# STM.net
KiCad netlist of a schematic drawn in EAGLE
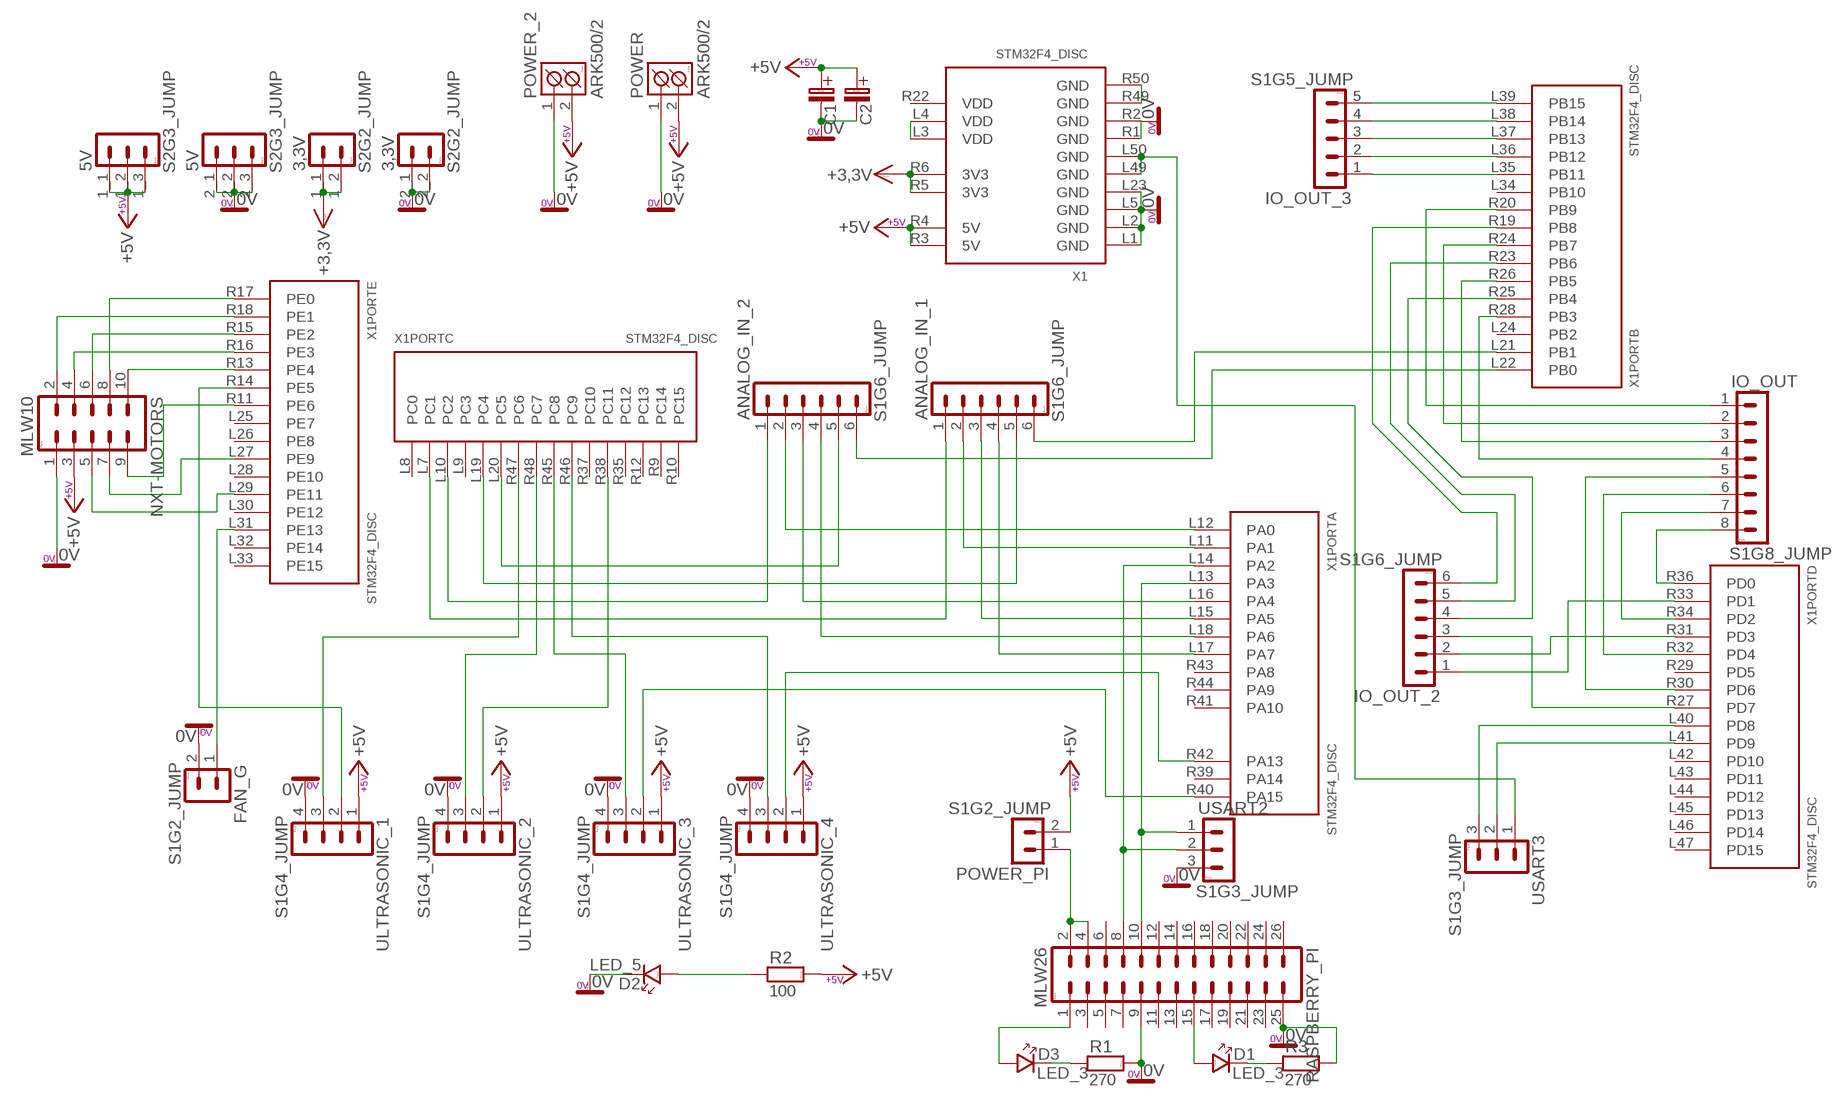
[diagram p0: schematic, sheet 1]

(export (version "E")
  (design (tool "Eeschema 10.0.6"))
  (components
    (comp (ref "3,3V")
      (value "S2G2_JUMP")
      (footprint "eagle-import:S2G2_JUM")
      (libsource (lib "eagle-import") (part "S2G2_JUMP"))
    )
    (comp (ref "5V")
      (value "S2G3_JUMP")
      (footprint "eagle-import:S2G3_JUM")
      (libsource (lib "eagle-import") (part "S2G3_JUMP"))
    )
    (comp (ref "ANALOG_IN_1")
      (value "S1G6_JUMP")
      (footprint "eagle-import:S1G6_JUM")
      (libsource (lib "eagle-import") (part "S1G6_JUMP"))
    )
    (comp (ref "ANALOG_IN_2")
      (value "S1G6_JUMP")
      (footprint "eagle-import:S1G6_JUM")
      (libsource (lib "eagle-import") (part "S1G6_JUMP"))
    )
    (comp (ref "C1")
      (value "#_RADIAL_POUZDRA5")
      (footprint "eagle-import:C_EL_5")
      (libsource (lib "eagle-import") (part "#_RADIAL_POUZDRA5"))
    )
    (comp (ref "C2")
      (value "#_RADIAL_POUZDRA5")
      (footprint "eagle-import:C_EL_5")
      (libsource (lib "eagle-import") (part "#_RADIAL_POUZDRA5"))
    )
    (comp (ref "D1")
      (value "LED_3")
      (footprint "eagle-import:LED_3")
      (libsource (lib "eagle-import") (part "LED_3"))
    )
    (comp (ref "D2")
      (value "LED_5")
      (footprint "eagle-import:LED_5")
      (libsource (lib "eagle-import") (part "LED_5"))
    )
    (comp (ref "D3")
      (value "LED_3")
      (footprint "eagle-import:LED_3")
      (libsource (lib "eagle-import") (part "LED_3"))
    )
    (comp (ref "FAN_G")
      (value "S1G2_JUMP")
      (footprint "eagle-import:S1G2_JUM")
      (libsource (lib "eagle-import") (part "S1G2_JUMP"))
    )
    (comp (ref "IO_OUT")
      (value "S1G8_JUMP")
      (footprint "eagle-import:S1G8_JUM")
      (libsource (lib "eagle-import") (part "S1G8_JUMP"))
    )
    (comp (ref "IO_OUT_2")
      (value "S1G6_JUMP")
      (footprint "eagle-import:S1G6_JUM")
      (libsource (lib "eagle-import") (part "S1G6_JUMP"))
    )
    (comp (ref "IO_OUT_3")
      (value "S1G5_JUMP")
      (footprint "eagle-import:S1G5_JUM")
      (libsource (lib "eagle-import") (part "S1G5_JUMP"))
    )
    (comp (ref "NXT-MOTORS")
      (value "MLW10")
      (footprint "eagle-import:MLW10G")
      (libsource (lib "eagle-import") (part "MLW10"))
    )
    (comp (ref "POWER")
      (value "ARK500/2")
      (footprint "eagle-import:ARK500_2")
      (libsource (lib "eagle-import") (part "ARK500/2"))
    )
    (comp (ref "POWER_2")
      (value "ARK500/2")
      (footprint "eagle-import:ARK500_2")
      (libsource (lib "eagle-import") (part "ARK500/2"))
    )
    (comp (ref "POWER_PI")
      (value "S1G2_JUMP")
      (footprint "eagle-import:S1G2_JUM")
      (libsource (lib "eagle-import") (part "S1G2_JUMP"))
    )
    (comp (ref "R1")
      (value "270")
      (footprint "eagle-import:R_7,5")
      (libsource (lib "eagle-import") (part "4K7"))
    )
    (comp (ref "R2")
      (value "100")
      (footprint "eagle-import:R_7,5")
      (libsource (lib "eagle-import") (part "100R"))
    )
    (comp (ref "R3")
      (value "270")
      (footprint "eagle-import:R_7,5")
      (libsource (lib "eagle-import") (part "4K7"))
    )
    (comp (ref "RASPBERRY_PI")
      (value "MLW26")
      (footprint "eagle-import:MLW26G")
      (libsource (lib "eagle-import") (part "MLW26"))
    )
    (comp (ref "ULTRASONIC_1")
      (value "S1G4_JUMP")
      (footprint "eagle-import:S1G4_JUM")
      (libsource (lib "eagle-import") (part "S1G4_JUMP"))
    )
    (comp (ref "ULTRASONIC_2")
      (value "S1G4_JUMP")
      (footprint "eagle-import:S1G4_JUM")
      (libsource (lib "eagle-import") (part "S1G4_JUMP"))
    )
    (comp (ref "ULTRASONIC_3")
      (value "S1G4_JUMP")
      (footprint "eagle-import:S1G4_JUM")
      (libsource (lib "eagle-import") (part "S1G4_JUMP"))
    )
    (comp (ref "ULTRASONIC_4")
      (value "S1G4_JUMP")
      (footprint "eagle-import:S1G4_JUM")
      (libsource (lib "eagle-import") (part "S1G4_JUMP"))
    )
    (comp (ref "USART2")
      (value "S1G3_JUMP")
      (footprint "eagle-import:S1G3_JUM")
      (libsource (lib "eagle-import") (part "S1G3_JUMP"))
    )
    (comp (ref "USART3")
      (value "S1G3_JUMP")
      (footprint "eagle-import:S1G3_JUM")
      (libsource (lib "eagle-import") (part "S1G3_JUMP"))
    )
    (comp (ref "X1")
      (value "STM32F4_DISC")
      (footprint "eagle-import:STM32F4_DISC")
      (libsource (lib "eagle-import") (part "STM32F4_DISC"))
    )
  )
  (nets
    (net (code "1") (name "+3,3V") (class "Default")
      (node (ref "3,3V") (pin "1_1") (pinfunction "1_1_1") (pintype "passive"))
      (node (ref "3,3V") (pin "1_2") (pinfunction "2_1_2") (pintype "passive"))
      (node (ref "X1") (pin "R5") (pinfunction "3V3_R5") (pintype "power_in"))
      (node (ref "X1") (pin "R6") (pinfunction "3V3_R6") (pintype "power_in"))
    )
    (net (code "2") (name "+5V") (class "Default")
      (node (ref "5V") (pin "1_1") (pinfunction "1_1_1") (pintype "passive"))
      (node (ref "5V") (pin "1_2") (pinfunction "2_1_2") (pintype "passive"))
      (node (ref "5V") (pin "1_3") (pinfunction "3_1_3") (pintype "passive"))
      (node (ref "C1") (pin "C+") (pinfunction "C_EL+_C+") (pintype "passive"))
      (node (ref "C2") (pin "C+") (pinfunction "C_EL+_C+") (pintype "passive"))
      (node (ref "NXT-MOTORS") (pin "3") (pinfunction "3_3") (pintype "passive"))
      (node (ref "POWER") (pin "2") (pinfunction "K2_2") (pintype "passive"))
      (node (ref "POWER_2") (pin "2") (pinfunction "K2_2") (pintype "passive"))
      (node (ref "POWER_PI") (pin "2") (pinfunction "2_2") (pintype "passive"))
      (node (ref "R2") (pin "2") (pinfunction "2_2") (pintype "passive"))
      (node (ref "ULTRASONIC_1") (pin "1") (pinfunction "1_1") (pintype "passive"))
      (node (ref "ULTRASONIC_2") (pin "1") (pinfunction "1_1") (pintype "passive"))
      (node (ref "ULTRASONIC_3") (pin "1") (pinfunction "1_1") (pintype "passive"))
      (node (ref "ULTRASONIC_4") (pin "1") (pinfunction "1_1") (pintype "passive"))
      (node (ref "X1") (pin "R3") (pinfunction "5V_R3") (pintype "power_in"))
      (node (ref "X1") (pin "R4") (pinfunction "5V_R4") (pintype "power_in"))
    )
    (net (code "3") (name "/VDD") (class "Default")
      (node (ref "X1") (pin "R22") (pinfunction "VDD_R22") (pintype "power_in"))
    )
    (net (code "4") (name "0V") (class "Default")
      (node (ref "3,3V") (pin "2_1") (pinfunction "1_2_1") (pintype "passive"))
      (node (ref "3,3V") (pin "2_2") (pinfunction "2_2_2") (pintype "passive"))
      (node (ref "5V") (pin "2_1") (pinfunction "1_2_1") (pintype "passive"))
      (node (ref "5V") (pin "2_2") (pinfunction "2_2_2") (pintype "passive"))
      (node (ref "5V") (pin "2_3") (pinfunction "3_2_3") (pintype "passive"))
      (node (ref "C1") (pin "C-") (pinfunction "C_EL-_C-") (pintype "passive"))
      (node (ref "C2") (pin "C-") (pinfunction "C_EL-_C-") (pintype "passive"))
      (node (ref "D2") (pin "K") (pinfunction "K_K") (pintype "passive"))
      (node (ref "FAN_G") (pin "2") (pinfunction "2_2") (pintype "passive"))
      (node (ref "NXT-MOTORS") (pin "1") (pinfunction "1_1") (pintype "passive"))
      (node (ref "POWER") (pin "1") (pinfunction "K1_1") (pintype "passive"))
      (node (ref "POWER_2") (pin "1") (pinfunction "K1_1") (pintype "passive"))
      (node (ref "R1") (pin "2") (pinfunction "2_2") (pintype "passive"))
      (node (ref "R3") (pin "2") (pinfunction "2_2") (pintype "passive"))
      (node (ref "RASPBERRY_PI") (pin "25") (pinfunction "25_25") (pintype "passive"))
      (node (ref "RASPBERRY_PI") (pin "9") (pinfunction "9_9") (pintype "passive"))
      (node (ref "ULTRASONIC_1") (pin "4") (pinfunction "4_4") (pintype "passive"))
      (node (ref "ULTRASONIC_2") (pin "4") (pinfunction "4_4") (pintype "passive"))
      (node (ref "ULTRASONIC_3") (pin "4") (pinfunction "4_4") (pintype "passive"))
      (node (ref "ULTRASONIC_4") (pin "4") (pinfunction "4_4") (pintype "passive"))
      (node (ref "USART2") (pin "3") (pinfunction "3_3") (pintype "passive"))
      (node (ref "X1") (pin "L1") (pinfunction "GND_L1") (pintype "power_in"))
      (node (ref "X1") (pin "L2") (pinfunction "GND_L2") (pintype "power_in"))
      (node (ref "X1") (pin "L23") (pinfunction "GND_L23") (pintype "power_in"))
      (node (ref "X1") (pin "L5") (pinfunction "GND_L5") (pintype "power_in"))
      (node (ref "X1") (pin "R1") (pinfunction "GND_R1") (pintype "power_in"))
      (node (ref "X1") (pin "R2") (pinfunction "GND_R2") (pintype "power_in"))
    )
    (net (code "5") (name "Net-(D1-PadA)") (class "Default")
      (node (ref "D1") (pin "A") (pinfunction "A_A") (pintype "passive"))
      (node (ref "RASPBERRY_PI") (pin "15") (pinfunction "15_15") (pintype "passive"))
    )
    (net (code "6") (name "Net-(D1-PadK)") (class "Default")
      (node (ref "D1") (pin "K") (pinfunction "K_K") (pintype "passive"))
      (node (ref "R3") (pin "1") (pinfunction "1_1") (pintype "passive"))
    )
    (net (code "7") (name "Net-(D2-PadA)") (class "Default")
      (node (ref "D2") (pin "A") (pinfunction "A_A") (pintype "passive"))
      (node (ref "R2") (pin "1") (pinfunction "1_1") (pintype "passive"))
    )
    (net (code "8") (name "Net-(D3-PadA)") (class "Default")
      (node (ref "D3") (pin "A") (pinfunction "A_A") (pintype "passive"))
      (node (ref "RASPBERRY_PI") (pin "1") (pinfunction "1_1") (pintype "passive"))
    )
    (net (code "9") (name "Net-(D3-PadK)") (class "Default")
      (node (ref "D3") (pin "K") (pinfunction "K_K") (pintype "passive"))
      (node (ref "R1") (pin "1") (pinfunction "1_1") (pintype "passive"))
    )
    (net (code "10") (name "Net-(POWER_PI-Pad1)") (class "Default")
      (node (ref "POWER_PI") (pin "1") (pinfunction "1_1") (pintype "passive"))
      (node (ref "RASPBERRY_PI") (pin "2") (pinfunction "2_2") (pintype "passive"))
      (node (ref "RASPBERRY_PI") (pin "4") (pinfunction "4_4") (pintype "passive"))
    )
    (net (code "11") (name "Net-(USART3-Pad1)") (class "Default")
      (node (ref "USART3") (pin "1") (pinfunction "1_1") (pintype "passive"))
      (node (ref "X1") (pin "L49") (pinfunction "GND_L49") (pintype "power_in"))
      (node (ref "X1") (pin "L50") (pinfunction "GND_L50") (pintype "power_in"))
    )
    (net (code "12") (name "Net-(X1A-PA0)") (class "Default")
      (node (ref "ANALOG_IN_2") (pin "2") (pinfunction "2_2") (pintype "passive"))
      (node (ref "X1") (pin "L12") (pinfunction "PA0_L12") (pintype "bidirectional"))
    )
    (net (code "13") (name "Net-(X1A-PA1)") (class "Default")
      (node (ref "ANALOG_IN_1") (pin "2") (pinfunction "2_2") (pintype "passive"))
      (node (ref "X1") (pin "L11") (pinfunction "PA1_L11") (pintype "bidirectional"))
    )
    (net (code "14") (name "Net-(X1A-PA2)") (class "Default")
      (node (ref "RASPBERRY_PI") (pin "8") (pinfunction "8_8") (pintype "passive"))
      (node (ref "USART2") (pin "2") (pinfunction "2_2") (pintype "passive"))
      (node (ref "X1") (pin "L14") (pinfunction "PA2_L14") (pintype "bidirectional"))
    )
    (net (code "15") (name "Net-(X1A-PA3)") (class "Default")
      (node (ref "RASPBERRY_PI") (pin "10") (pinfunction "10_10") (pintype "passive"))
      (node (ref "USART2") (pin "1") (pinfunction "1_1") (pintype "passive"))
      (node (ref "X1") (pin "L13") (pinfunction "PA3_L13") (pintype "bidirectional"))
    )
    (net (code "16") (name "Net-(X1A-PA4)") (class "Default")
      (node (ref "ANALOG_IN_2") (pin "3") (pinfunction "3_3") (pintype "passive"))
      (node (ref "X1") (pin "L16") (pinfunction "PA4_L16") (pintype "bidirectional"))
    )
    (net (code "17") (name "Net-(X1A-PA5)") (class "Default")
      (node (ref "ANALOG_IN_1") (pin "3") (pinfunction "3_3") (pintype "passive"))
      (node (ref "X1") (pin "L15") (pinfunction "PA5_L15") (pintype "bidirectional"))
    )
    (net (code "18") (name "Net-(X1A-PA6)") (class "Default")
      (node (ref "ANALOG_IN_2") (pin "4") (pinfunction "4_4") (pintype "passive"))
      (node (ref "X1") (pin "L18") (pinfunction "PA6_L18") (pintype "bidirectional"))
    )
    (net (code "19") (name "Net-(X1A-PA7)") (class "Default")
      (node (ref "ANALOG_IN_1") (pin "4") (pinfunction "4_4") (pintype "passive"))
      (node (ref "X1") (pin "L17") (pinfunction "PA7_L17") (pintype "bidirectional"))
    )
    (net (code "20") (name "Net-(X1A-PA13)") (class "Default")
      (node (ref "ULTRASONIC_4") (pin "2") (pinfunction "2_2") (pintype "passive"))
      (node (ref "X1") (pin "R42") (pinfunction "PA13_R42") (pintype "bidirectional"))
    )
    (net (code "21") (name "Net-(X1A-PA15)") (class "Default")
      (node (ref "ULTRASONIC_3") (pin "2") (pinfunction "2_2") (pintype "passive"))
      (node (ref "X1") (pin "R40") (pinfunction "PA15_R40") (pintype "bidirectional"))
    )
    (net (code "22") (name "Net-(X1B-PB0)") (class "Default")
      (node (ref "ANALOG_IN_2") (pin "6") (pinfunction "6_6") (pintype "passive"))
      (node (ref "X1") (pin "L22") (pinfunction "PB0_L22") (pintype "bidirectional"))
    )
    (net (code "23") (name "Net-(X1B-PB1)") (class "Default")
      (node (ref "ANALOG_IN_1") (pin "6") (pinfunction "6_6") (pintype "passive"))
      (node (ref "X1") (pin "L21") (pinfunction "PB1_L21") (pintype "bidirectional"))
    )
    (net (code "24") (name "Net-(X1B-PB3)") (class "Default")
      (node (ref "IO_OUT") (pin "4") (pinfunction "4_4") (pintype "passive"))
      (node (ref "X1") (pin "R28") (pinfunction "PB3_R28") (pintype "bidirectional"))
    )
    (net (code "25") (name "Net-(X1B-PB4)") (class "Default")
      (node (ref "IO_OUT_2") (pin "4") (pinfunction "4_4") (pintype "passive"))
      (node (ref "X1") (pin "R25") (pinfunction "PB4_R25") (pintype "bidirectional"))
    )
    (net (code "26") (name "Net-(X1B-PB5)") (class "Default")
      (node (ref "IO_OUT") (pin "3") (pinfunction "3_3") (pintype "passive"))
      (node (ref "X1") (pin "R26") (pinfunction "PB5_R26") (pintype "bidirectional"))
    )
    (net (code "27") (name "Net-(X1B-PB6)") (class "Default")
      (node (ref "IO_OUT_2") (pin "5") (pinfunction "5_5") (pintype "passive"))
      (node (ref "X1") (pin "R23") (pinfunction "PB6_R23") (pintype "bidirectional"))
    )
    (net (code "28") (name "Net-(X1B-PB7)") (class "Default")
      (node (ref "IO_OUT") (pin "2") (pinfunction "2_2") (pintype "passive"))
      (node (ref "X1") (pin "R24") (pinfunction "PB7_R24") (pintype "bidirectional"))
    )
    (net (code "29") (name "Net-(X1B-PB8)") (class "Default")
      (node (ref "IO_OUT_2") (pin "6") (pinfunction "6_6") (pintype "passive"))
      (node (ref "X1") (pin "R19") (pinfunction "PB8_R19") (pintype "bidirectional"))
    )
    (net (code "30") (name "Net-(X1B-PB9)") (class "Default")
      (node (ref "IO_OUT") (pin "1") (pinfunction "1_1") (pintype "passive"))
      (node (ref "X1") (pin "R20") (pinfunction "PB9_R20") (pintype "bidirectional"))
    )
    (net (code "31") (name "Net-(X1B-PB11)") (class "Default")
      (node (ref "IO_OUT_3") (pin "1") (pinfunction "1_1") (pintype "passive"))
      (node (ref "X1") (pin "L35") (pinfunction "PB11_L35") (pintype "bidirectional"))
    )
    (net (code "32") (name "Net-(X1B-PB12)") (class "Default")
      (node (ref "IO_OUT_3") (pin "2") (pinfunction "2_2") (pintype "passive"))
      (node (ref "X1") (pin "L36") (pinfunction "PB12_L36") (pintype "bidirectional"))
    )
    (net (code "33") (name "Net-(X1B-PB13)") (class "Default")
      (node (ref "IO_OUT_3") (pin "3") (pinfunction "3_3") (pintype "passive"))
      (node (ref "X1") (pin "L37") (pinfunction "PB13_L37") (pintype "bidirectional"))
    )
    (net (code "34") (name "Net-(X1B-PB14)") (class "Default")
      (node (ref "IO_OUT_3") (pin "4") (pinfunction "4_4") (pintype "passive"))
      (node (ref "X1") (pin "L38") (pinfunction "PB14_L38") (pintype "bidirectional"))
    )
    (net (code "35") (name "Net-(X1B-PB15)") (class "Default")
      (node (ref "IO_OUT_3") (pin "5") (pinfunction "5_5") (pintype "passive"))
      (node (ref "X1") (pin "L39") (pinfunction "PB15_L39") (pintype "bidirectional"))
    )
    (net (code "36") (name "Net-(X1C-PC1)") (class "Default")
      (node (ref "ANALOG_IN_1") (pin "1") (pinfunction "1_1") (pintype "passive"))
      (node (ref "X1") (pin "L7") (pinfunction "PC1_L7") (pintype "bidirectional"))
    )
    (net (code "37") (name "Net-(X1C-PC2)") (class "Default")
      (node (ref "ANALOG_IN_2") (pin "1") (pinfunction "1_1") (pintype "passive"))
      (node (ref "X1") (pin "L10") (pinfunction "PC2_L10") (pintype "bidirectional"))
    )
    (net (code "38") (name "Net-(X1C-PC4)") (class "Default")
      (node (ref "ANALOG_IN_1") (pin "5") (pinfunction "5_5") (pintype "passive"))
      (node (ref "X1") (pin "L19") (pinfunction "PC4_L19") (pintype "bidirectional"))
    )
    (net (code "39") (name "Net-(X1C-PC5)") (class "Default")
      (node (ref "ANALOG_IN_2") (pin "5") (pinfunction "5_5") (pintype "passive"))
      (node (ref "X1") (pin "L20") (pinfunction "PC5_L20") (pintype "bidirectional"))
    )
    (net (code "40") (name "Net-(X1C-PC6)") (class "Default")
      (node (ref "ULTRASONIC_1") (pin "3") (pinfunction "3_3") (pintype "passive"))
      (node (ref "X1") (pin "R47") (pinfunction "PC6_R47") (pintype "bidirectional"))
    )
    (net (code "41") (name "Net-(X1C-PC7)") (class "Default")
      (node (ref "ULTRASONIC_2") (pin "3") (pinfunction "3_3") (pintype "passive"))
      (node (ref "X1") (pin "R48") (pinfunction "PC7_R48") (pintype "bidirectional"))
    )
    (net (code "42") (name "Net-(X1C-PC8)") (class "Default")
      (node (ref "ULTRASONIC_3") (pin "3") (pinfunction "3_3") (pintype "passive"))
      (node (ref "X1") (pin "R45") (pinfunction "PC8_R45") (pintype "bidirectional"))
    )
    (net (code "43") (name "Net-(X1C-PC9)") (class "Default")
      (node (ref "ULTRASONIC_4") (pin "3") (pinfunction "3_3") (pintype "passive"))
      (node (ref "X1") (pin "R46") (pinfunction "PC9_R46") (pintype "bidirectional"))
    )
    (net (code "44") (name "Net-(X1C-PC11)") (class "Default")
      (node (ref "ULTRASONIC_2") (pin "2") (pinfunction "2_2") (pintype "passive"))
      (node (ref "X1") (pin "R38") (pinfunction "PC11_R38") (pintype "bidirectional"))
    )
    (net (code "45") (name "Net-(X1D-PD0)") (class "Default")
      (node (ref "IO_OUT") (pin "8") (pinfunction "8_8") (pintype "passive"))
      (node (ref "X1") (pin "R36") (pinfunction "PD0_R36") (pintype "bidirectional"))
    )
    (net (code "46") (name "Net-(X1D-PD1)") (class "Default")
      (node (ref "IO_OUT_2") (pin "1") (pinfunction "1_1") (pintype "passive"))
      (node (ref "X1") (pin "R33") (pinfunction "PD1_R33") (pintype "bidirectional"))
    )
    (net (code "47") (name "Net-(X1D-PD2)") (class "Default")
      (node (ref "IO_OUT") (pin "7") (pinfunction "7_7") (pintype "passive"))
      (node (ref "X1") (pin "R34") (pinfunction "PD2_R34") (pintype "bidirectional"))
    )
    (net (code "48") (name "Net-(X1D-PD3)") (class "Default")
      (node (ref "IO_OUT_2") (pin "2") (pinfunction "2_2") (pintype "passive"))
      (node (ref "X1") (pin "R31") (pinfunction "PD3_R31") (pintype "bidirectional"))
    )
    (net (code "49") (name "Net-(X1D-PD4)") (class "Default")
      (node (ref "IO_OUT") (pin "6") (pinfunction "6_6") (pintype "passive"))
      (node (ref "X1") (pin "R32") (pinfunction "PD4_R32") (pintype "bidirectional"))
    )
    (net (code "50") (name "Net-(X1D-PD6)") (class "Default")
      (node (ref "IO_OUT") (pin "5") (pinfunction "5_5") (pintype "passive"))
      (node (ref "X1") (pin "R30") (pinfunction "PD6_R30") (pintype "bidirectional"))
    )
    (net (code "51") (name "Net-(X1D-PD7)") (class "Default")
      (node (ref "IO_OUT_2") (pin "3") (pinfunction "3_3") (pintype "passive"))
      (node (ref "X1") (pin "R27") (pinfunction "PD7_R27") (pintype "bidirectional"))
    )
    (net (code "52") (name "Net-(X1D-PD8)") (class "Default")
      (node (ref "USART3") (pin "3") (pinfunction "3_3") (pintype "passive"))
      (node (ref "X1") (pin "L40") (pinfunction "PD8_L40") (pintype "bidirectional"))
    )
    (net (code "53") (name "Net-(X1D-PD9)") (class "Default")
      (node (ref "USART3") (pin "2") (pinfunction "2_2") (pintype "passive"))
      (node (ref "X1") (pin "L41") (pinfunction "PD9_L41") (pintype "bidirectional"))
    )
    (net (code "54") (name "Net-(X1E-PE0)") (class "Default")
      (node (ref "NXT-MOTORS") (pin "8") (pinfunction "8_8") (pintype "passive"))
      (node (ref "X1") (pin "R17") (pinfunction "PE0_R17") (pintype "bidirectional"))
    )
    (net (code "55") (name "Net-(X1E-PE1)") (class "Default")
      (node (ref "NXT-MOTORS") (pin "2") (pinfunction "2_2") (pintype "passive"))
      (node (ref "X1") (pin "R18") (pinfunction "PE1_R18") (pintype "bidirectional"))
    )
    (net (code "56") (name "Net-(X1E-PE2)") (class "Default")
      (node (ref "NXT-MOTORS") (pin "6") (pinfunction "6_6") (pintype "passive"))
      (node (ref "X1") (pin "R15") (pinfunction "PE2_R15") (pintype "bidirectional"))
    )
    (net (code "57") (name "Net-(X1E-PE3)") (class "Default")
      (node (ref "NXT-MOTORS") (pin "4") (pinfunction "4_4") (pintype "passive"))
      (node (ref "X1") (pin "R16") (pinfunction "PE3_R16") (pintype "bidirectional"))
    )
    (net (code "58") (name "Net-(X1E-PE4)") (class "Default")
      (node (ref "NXT-MOTORS") (pin "10") (pinfunction "10_10") (pintype "passive"))
      (node (ref "X1") (pin "R13") (pinfunction "PE4_R13") (pintype "bidirectional"))
    )
    (net (code "59") (name "Net-(X1E-PE5)") (class "Default")
      (node (ref "ULTRASONIC_1") (pin "2") (pinfunction "2_2") (pintype "passive"))
      (node (ref "X1") (pin "R14") (pinfunction "PE5_R14") (pintype "bidirectional"))
    )
    (net (code "60") (name "Net-(X1E-PE6)") (class "Default")
      (node (ref "NXT-MOTORS") (pin "9") (pinfunction "9_9") (pintype "passive"))
      (node (ref "X1") (pin "R11") (pinfunction "PE6_R11") (pintype "bidirectional"))
    )
    (net (code "61") (name "Net-(X1E-PE9)") (class "Default")
      (node (ref "NXT-MOTORS") (pin "7") (pinfunction "7_7") (pintype "passive"))
      (node (ref "X1") (pin "L27") (pinfunction "PE9_L27") (pintype "bidirectional"))
    )
    (net (code "62") (name "Net-(X1E-PE11)") (class "Default")
      (node (ref "NXT-MOTORS") (pin "5") (pinfunction "5_5") (pintype "passive"))
      (node (ref "X1") (pin "L29") (pinfunction "PE11_L29") (pintype "bidirectional"))
    )
    (net (code "63") (name "Net-(X1E-PE13)") (class "Default")
      (node (ref "FAN_G") (pin "1") (pinfunction "1_1") (pintype "passive"))
      (node (ref "X1") (pin "L31") (pinfunction "PE13_L31") (pintype "bidirectional"))
    )
    (net (code "64") (name "Net-(X1G-GND-PadR49)") (class "Default")
      (node (ref "X1") (pin "R49") (pinfunction "GND_R49") (pintype "power_in"))
      (node (ref "X1") (pin "R50") (pinfunction "GND_R50") (pintype "power_in"))
    )
    (net (code "65") (name "Net-(X1G-VDD-PadL3)") (class "Default")
      (node (ref "X1") (pin "L3") (pinfunction "VDD_L3") (pintype "power_in"))
      (node (ref "X1") (pin "L4") (pinfunction "VDD_L4") (pintype "power_in"))
    )
    (net (code "66") (name "unconnected-(RASPBERRY_PI-Pad3)") (class "Default")
      (node (ref "RASPBERRY_PI") (pin "3") (pinfunction "3_3") (pintype "passive"))
    )
    (net (code "67") (name "unconnected-(RASPBERRY_PI-Pad5)") (class "Default")
      (node (ref "RASPBERRY_PI") (pin "5") (pinfunction "5_5") (pintype "passive"))
    )
    (net (code "68") (name "unconnected-(RASPBERRY_PI-Pad6)") (class "Default")
      (node (ref "RASPBERRY_PI") (pin "6") (pinfunction "6_6") (pintype "passive"))
    )
    (net (code "69") (name "unconnected-(RASPBERRY_PI-Pad7)") (class "Default")
      (node (ref "RASPBERRY_PI") (pin "7") (pinfunction "7_7") (pintype "passive"))
    )
    (net (code "70") (name "unconnected-(RASPBERRY_PI-Pad11)") (class "Default")
      (node (ref "RASPBERRY_PI") (pin "11") (pinfunction "11_11") (pintype "passive"))
    )
    (net (code "71") (name "unconnected-(RASPBERRY_PI-Pad12)") (class "Default")
      (node (ref "RASPBERRY_PI") (pin "12") (pinfunction "12_12") (pintype "passive"))
    )
    (net (code "72") (name "unconnected-(RASPBERRY_PI-Pad13)") (class "Default")
      (node (ref "RASPBERRY_PI") (pin "13") (pinfunction "13_13") (pintype "passive"))
    )
    (net (code "73") (name "unconnected-(RASPBERRY_PI-Pad14)") (class "Default")
      (node (ref "RASPBERRY_PI") (pin "14") (pinfunction "14_14") (pintype "passive"))
    )
    (net (code "74") (name "unconnected-(RASPBERRY_PI-Pad16)") (class "Default")
      (node (ref "RASPBERRY_PI") (pin "16") (pinfunction "16_16") (pintype "passive"))
    )
    (net (code "75") (name "unconnected-(RASPBERRY_PI-Pad17)") (class "Default")
      (node (ref "RASPBERRY_PI") (pin "17") (pinfunction "17_17") (pintype "passive"))
    )
    (net (code "76") (name "unconnected-(RASPBERRY_PI-Pad18)") (class "Default")
      (node (ref "RASPBERRY_PI") (pin "18") (pinfunction "18_18") (pintype "passive"))
    )
    (net (code "77") (name "unconnected-(RASPBERRY_PI-Pad19)") (class "Default")
      (node (ref "RASPBERRY_PI") (pin "19") (pinfunction "19_19") (pintype "passive"))
    )
    (net (code "78") (name "unconnected-(RASPBERRY_PI-Pad20)") (class "Default")
      (node (ref "RASPBERRY_PI") (pin "20") (pinfunction "20_20") (pintype "passive"))
    )
    (net (code "79") (name "unconnected-(RASPBERRY_PI-Pad21)") (class "Default")
      (node (ref "RASPBERRY_PI") (pin "21") (pinfunction "21_21") (pintype "passive"))
    )
    (net (code "80") (name "unconnected-(RASPBERRY_PI-Pad22)") (class "Default")
      (node (ref "RASPBERRY_PI") (pin "22") (pinfunction "22_22") (pintype "passive"))
    )
    (net (code "81") (name "unconnected-(RASPBERRY_PI-Pad23)") (class "Default")
      (node (ref "RASPBERRY_PI") (pin "23") (pinfunction "23_23") (pintype "passive"))
    )
    (net (code "82") (name "unconnected-(RASPBERRY_PI-Pad24)") (class "Default")
      (node (ref "RASPBERRY_PI") (pin "24") (pinfunction "24_24") (pintype "passive"))
    )
    (net (code "83") (name "unconnected-(RASPBERRY_PI-Pad26)") (class "Default")
      (node (ref "RASPBERRY_PI") (pin "26") (pinfunction "26_26") (pintype "passive"))
    )
    (net (code "84") (name "unconnected-(X1A-PA8-PadR43)") (class "Default")
      (node (ref "X1") (pin "R43") (pinfunction "PA8_R43") (pintype "bidirectional"))
    )
    (net (code "85") (name "unconnected-(X1A-PA9-PadR44)") (class "Default")
      (node (ref "X1") (pin "R44") (pinfunction "PA9_R44") (pintype "bidirectional"))
    )
    (net (code "86") (name "unconnected-(X1A-PA10-PadR41)") (class "Default")
      (node (ref "X1") (pin "R41") (pinfunction "PA10_R41") (pintype "bidirectional"))
    )
    (net (code "87") (name "unconnected-(X1A-PA14-PadR39)") (class "Default")
      (node (ref "X1") (pin "R39") (pinfunction "PA14_R39") (pintype "bidirectional"))
    )
    (net (code "88") (name "unconnected-(X1B-PB2-PadL24)") (class "Default")
      (node (ref "X1") (pin "L24") (pinfunction "PB2_L24") (pintype "bidirectional"))
    )
    (net (code "89") (name "unconnected-(X1B-PB10-PadL34)") (class "Default")
      (node (ref "X1") (pin "L34") (pinfunction "PB10_L34") (pintype "bidirectional"))
    )
    (net (code "90") (name "unconnected-(X1C-PC0-PadL8)") (class "Default")
      (node (ref "X1") (pin "L8") (pinfunction "PC0_L8") (pintype "bidirectional"))
    )
    (net (code "91") (name "unconnected-(X1C-PC3-PadL9)") (class "Default")
      (node (ref "X1") (pin "L9") (pinfunction "PC3_L9") (pintype "bidirectional"))
    )
    (net (code "92") (name "unconnected-(X1C-PC10-PadR37)") (class "Default")
      (node (ref "X1") (pin "R37") (pinfunction "PC10_R37") (pintype "bidirectional"))
    )
    (net (code "93") (name "unconnected-(X1C-PC12-PadR35)") (class "Default")
      (node (ref "X1") (pin "R35") (pinfunction "PC12_R35") (pintype "bidirectional"))
    )
    (net (code "94") (name "unconnected-(X1C-PC13-PadR12)") (class "Default")
      (node (ref "X1") (pin "R12") (pinfunction "PC13_R12") (pintype "bidirectional"))
    )
    (net (code "95") (name "unconnected-(X1C-PC14-PadR9)") (class "Default")
      (node (ref "X1") (pin "R9") (pinfunction "PC14_R9") (pintype "bidirectional"))
    )
    (net (code "96") (name "unconnected-(X1C-PC15-PadR10)") (class "Default")
      (node (ref "X1") (pin "R10") (pinfunction "PC15_R10") (pintype "bidirectional"))
    )
    (net (code "97") (name "unconnected-(X1D-PD5-PadR29)") (class "Default")
      (node (ref "X1") (pin "R29") (pinfunction "PD5_R29") (pintype "bidirectional"))
    )
    (net (code "98") (name "unconnected-(X1D-PD10-PadL42)") (class "Default")
      (node (ref "X1") (pin "L42") (pinfunction "PD10_L42") (pintype "bidirectional"))
    )
    (net (code "99") (name "unconnected-(X1D-PD11-PadL43)") (class "Default")
      (node (ref "X1") (pin "L43") (pinfunction "PD11_L43") (pintype "bidirectional"))
    )
    (net (code "100") (name "unconnected-(X1D-PD12-PadL44)") (class "Default")
      (node (ref "X1") (pin "L44") (pinfunction "PD12_L44") (pintype "bidirectional"))
    )
    (net (code "101") (name "unconnected-(X1D-PD13-PadL45)") (class "Default")
      (node (ref "X1") (pin "L45") (pinfunction "PD13_L45") (pintype "bidirectional"))
    )
    (net (code "102") (name "unconnected-(X1D-PD14-PadL46)") (class "Default")
      (node (ref "X1") (pin "L46") (pinfunction "PD14_L46") (pintype "bidirectional"))
    )
    (net (code "103") (name "unconnected-(X1D-PD15-PadL47)") (class "Default")
      (node (ref "X1") (pin "L47") (pinfunction "PD15_L47") (pintype "bidirectional"))
    )
    (net (code "104") (name "unconnected-(X1E-PE7-PadL25)") (class "Default")
      (node (ref "X1") (pin "L25") (pinfunction "PE7_L25") (pintype "bidirectional"))
    )
    (net (code "105") (name "unconnected-(X1E-PE8-PadL26)") (class "Default")
      (node (ref "X1") (pin "L26") (pinfunction "PE8_L26") (pintype "bidirectional"))
    )
    (net (code "106") (name "unconnected-(X1E-PE10-PadL28)") (class "Default")
      (node (ref "X1") (pin "L28") (pinfunction "PE10_L28") (pintype "bidirectional"))
    )
    (net (code "107") (name "unconnected-(X1E-PE12-PadL30)") (class "Default")
      (node (ref "X1") (pin "L30") (pinfunction "PE12_L30") (pintype "bidirectional"))
    )
    (net (code "108") (name "unconnected-(X1E-PE14-PadL32)") (class "Default")
      (node (ref "X1") (pin "L32") (pinfunction "PE14_L32") (pintype "bidirectional"))
    )
    (net (code "109") (name "unconnected-(X1E-PE15-PadL33)") (class "Default")
      (node (ref "X1") (pin "L33") (pinfunction "PE15_L33") (pintype "bidirectional"))
    )
  )
)
